# Control.net
KiCad netlist of a schematic drawn in EAGLE
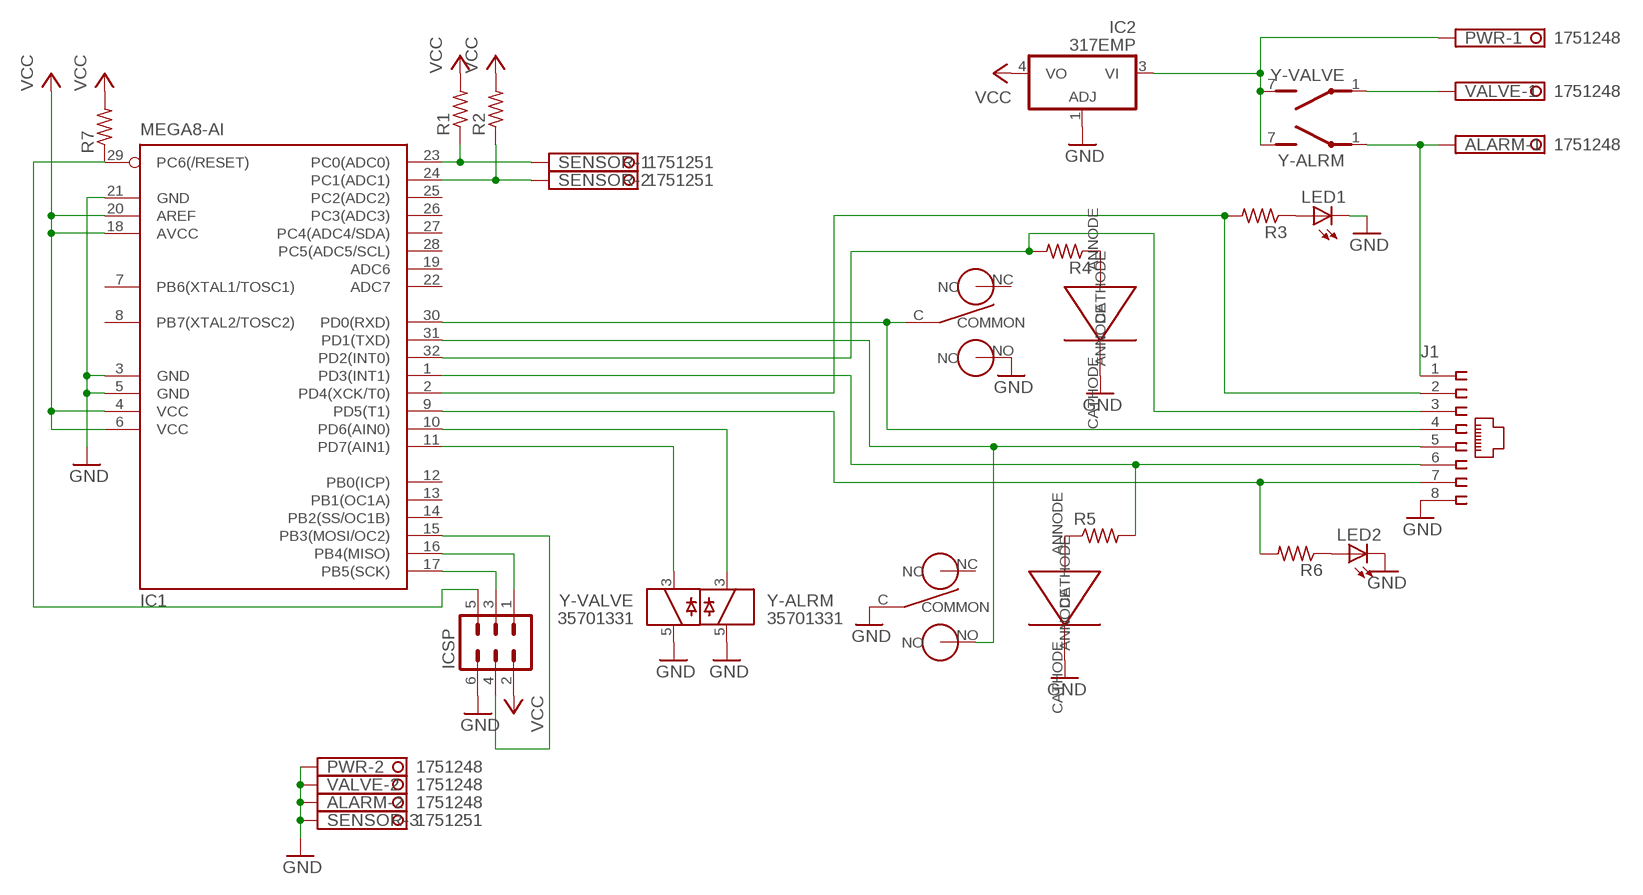
[diagram p0: schematic, sheet 1]

(export (version "E")
  (design (tool "Eeschema 10.0.6"))
  (components
    (comp (ref "ALARM")
      (value "1751248")
      (footprint "eagle-import:1751248")
      (libsource (lib "eagle-import") (part "1751248"))
    )
    (comp (ref "BUTTON1")
      (value "LED-BUTTON-16MM")
      (footprint "eagle-import:16MM")
      (libsource (lib "eagle-import") (part "LED-BUTTON-16MM"))
    )
    (comp (ref "BUTTON2")
      (value "LED-BUTTON-16MM")
      (footprint "eagle-import:16MM")
      (libsource (lib "eagle-import") (part "LED-BUTTON-16MM"))
    )
    (comp (ref "IC1")
      (value "MEGA8-AI")
      (footprint "eagle-import:TQFP32-08")
      (fields (field (name "MPN") "ATMEGA8-16AU"))
      (libsource (lib "eagle-import") (part "MEGA8-AI"))
    )
    (comp (ref "IC2")
      (value "317EMP")
      (footprint "eagle-import:SOT223")
      (libsource (lib "eagle-import") (part "317EMP"))
    )
    (comp (ref "ICSP")
      (value "MA03-2")
      (footprint "eagle-import:MA03-2")
      (libsource (lib "eagle-import") (part "MA03-2"))
    )
    (comp (ref "J1")
      (value "215877-7")
      (footprint "eagle-import:215877-7")
      (libsource (lib "eagle-import") (part "215877-7"))
    )
    (comp (ref "LED1")
      (value "LED5MM")
      (footprint "eagle-import:LED5MM")
      (libsource (lib "eagle-import") (part "LED5MM"))
    )
    (comp (ref "LED2")
      (value "LED5MM")
      (footprint "eagle-import:LED5MM")
      (libsource (lib "eagle-import") (part "LED5MM"))
    )
    (comp (ref "PWR")
      (value "1751248")
      (footprint "eagle-import:1751248")
      (libsource (lib "eagle-import") (part "1751248"))
    )
    (comp (ref "R1")
      (value "R-US_M0805")
      (footprint "eagle-import:M0805")
      (libsource (lib "eagle-import") (part "R-US_M0805"))
    )
    (comp (ref "R2")
      (value "R-US_M0805")
      (footprint "eagle-import:M0805")
      (libsource (lib "eagle-import") (part "R-US_M0805"))
    )
    (comp (ref "R3")
      (value "R-US_M0805")
      (footprint "eagle-import:M0805")
      (libsource (lib "eagle-import") (part "R-US_M0805"))
    )
    (comp (ref "R4")
      (value "R-US_M0805")
      (footprint "eagle-import:M0805")
      (libsource (lib "eagle-import") (part "R-US_M0805"))
    )
    (comp (ref "R5")
      (value "R-US_M0805")
      (footprint "eagle-import:M0805")
      (libsource (lib "eagle-import") (part "R-US_M0805"))
    )
    (comp (ref "R6")
      (value "R-US_M0805")
      (footprint "eagle-import:M0805")
      (libsource (lib "eagle-import") (part "R-US_M0805"))
    )
    (comp (ref "R7")
      (value "R-US_M0805")
      (footprint "eagle-import:M0805")
      (libsource (lib "eagle-import") (part "R-US_M0805"))
    )
    (comp (ref "SENSOR")
      (value "1751251")
      (footprint "eagle-import:1751251")
      (libsource (lib "eagle-import") (part "1751251"))
    )
    (comp (ref "VALVE")
      (value "1751248")
      (footprint "eagle-import:1751248")
      (libsource (lib "eagle-import") (part "1751248"))
    )
    (comp (ref "Y-ALRM")
      (value "35701331")
      (footprint "eagle-import:REED")
      (libsource (lib "eagle-import") (part "35701331"))
    )
    (comp (ref "Y-VALVE")
      (value "35701331")
      (footprint "eagle-import:REED")
      (libsource (lib "eagle-import") (part "35701331"))
    )
  )
  (nets
    (net (code "1") (name "GND") (class "Default")
      (node (ref "ALARM") (pin "2") (pinfunction "K_2") (pintype "passive"))
      (node (ref "BUTTON1") (pin "CATHODE") (pinfunction "CATHODE_CATHODE") (pintype "bidirectional"))
      (node (ref "BUTTON1") (pin "NO") (pinfunction "NO_NO") (pintype "bidirectional"))
      (node (ref "BUTTON2") (pin "C") (pinfunction "COMMON_C") (pintype "bidirectional"))
      (node (ref "BUTTON2") (pin "CATHODE") (pinfunction "CATHODE_CATHODE") (pintype "bidirectional"))
      (node (ref "IC1") (pin "21") (pinfunction "GND_21") (pintype "power_in"))
      (node (ref "IC1") (pin "3") (pinfunction "GND_3") (pintype "power_in"))
      (node (ref "IC1") (pin "5") (pinfunction "GND_5") (pintype "power_in"))
      (node (ref "IC2") (pin "1") (pinfunction "ADJ_1") (pintype "input"))
      (node (ref "ICSP") (pin "6") (pinfunction "6_6") (pintype "passive"))
      (node (ref "J1") (pin "8") (pinfunction "8_8") (pintype "passive"))
      (node (ref "LED1") (pin "K") (pinfunction "C_K") (pintype "passive"))
      (node (ref "LED2") (pin "K") (pinfunction "C_K") (pintype "passive"))
      (node (ref "PWR") (pin "2") (pinfunction "K_2") (pintype "passive"))
      (node (ref "SENSOR") (pin "3") (pinfunction "K_3") (pintype "passive"))
      (node (ref "VALVE") (pin "2") (pinfunction "K_2") (pintype "passive"))
      (node (ref "Y-ALRM") (pin "5") (pinfunction "5_5") (pintype "passive"))
      (node (ref "Y-VALVE") (pin "5") (pinfunction "5_5") (pintype "passive"))
    )
    (net (code "2") (name "Net-(ALARMA-K)") (class "Default")
      (node (ref "ALARM") (pin "1") (pinfunction "K_1") (pintype "passive"))
      (node (ref "J1") (pin "1") (pinfunction "1_1") (pintype "passive"))
      (node (ref "Y-ALRM") (pin "1") (pinfunction "P_1") (pintype "passive"))
    )
    (net (code "3") (name "Net-(BUTTON1-COMMON)") (class "Default")
      (node (ref "BUTTON1") (pin "C") (pinfunction "COMMON_C") (pintype "bidirectional"))
      (node (ref "IC1") (pin "30") (pinfunction "PD0(RXD)_30") (pintype "bidirectional"))
      (node (ref "J1") (pin "4") (pinfunction "4_4") (pintype "passive"))
    )
    (net (code "4") (name "Net-(BUTTON1-PadANNODE)") (class "Default")
      (node (ref "BUTTON1") (pin "ANNODE") (pinfunction "ANNODE_ANNODE") (pintype "bidirectional"))
      (node (ref "R4") (pin "1") (pinfunction "1_1") (pintype "passive"))
    )
    (net (code "5") (name "Net-(BUTTON2-PadANNODE)") (class "Default")
      (node (ref "BUTTON2") (pin "ANNODE") (pinfunction "ANNODE_ANNODE") (pintype "bidirectional"))
      (node (ref "R5") (pin "1") (pinfunction "1_1") (pintype "passive"))
    )
    (net (code "6") (name "Net-(IC1-PB3(MOSI{slash}OC2))") (class "Default")
      (node (ref "IC1") (pin "15") (pinfunction "PB3(MOSI/OC2)_15") (pintype "bidirectional"))
      (node (ref "ICSP") (pin "4") (pinfunction "4_4") (pintype "passive"))
    )
    (net (code "7") (name "Net-(IC1-PB4(MISO))") (class "Default")
      (node (ref "IC1") (pin "16") (pinfunction "PB4(MISO)_16") (pintype "bidirectional"))
      (node (ref "ICSP") (pin "1") (pinfunction "1_1") (pintype "passive"))
    )
    (net (code "8") (name "Net-(IC1-PB5(SCK))") (class "Default")
      (node (ref "IC1") (pin "17") (pinfunction "PB5(SCK)_17") (pintype "bidirectional"))
      (node (ref "ICSP") (pin "3") (pinfunction "3_3") (pintype "passive"))
    )
    (net (code "9") (name "Net-(IC1-PC0(ADC0))") (class "Default")
      (node (ref "IC1") (pin "23") (pinfunction "PC0(ADC0)_23") (pintype "bidirectional"))
      (node (ref "R1") (pin "1") (pinfunction "1_1") (pintype "passive"))
      (node (ref "SENSOR") (pin "1") (pinfunction "K_1") (pintype "passive"))
    )
    (net (code "10") (name "Net-(IC1-PC1(ADC1))") (class "Default")
      (node (ref "IC1") (pin "24") (pinfunction "PC1(ADC1)_24") (pintype "bidirectional"))
      (node (ref "R2") (pin "1") (pinfunction "1_1") (pintype "passive"))
      (node (ref "SENSOR") (pin "2") (pinfunction "K_2") (pintype "passive"))
    )
    (net (code "11") (name "Net-(IC1-PC6({slash}RESET))") (class "Default")
      (node (ref "IC1") (pin "29") (pinfunction "PC6(/RESET)_29") (pintype "bidirectional"))
      (node (ref "ICSP") (pin "5") (pinfunction "5_5") (pintype "passive"))
      (node (ref "R7") (pin "1") (pinfunction "1_1") (pintype "passive"))
    )
    (net (code "12") (name "Net-(IC1-PD1(TXD))") (class "Default")
      (node (ref "BUTTON2") (pin "NO") (pinfunction "NO_NO") (pintype "bidirectional"))
      (node (ref "IC1") (pin "31") (pinfunction "PD1(TXD)_31") (pintype "bidirectional"))
      (node (ref "J1") (pin "5") (pinfunction "5_5") (pintype "passive"))
    )
    (net (code "13") (name "Net-(IC1-PD2(INT0))") (class "Default")
      (node (ref "IC1") (pin "32") (pinfunction "PD2(INT0)_32") (pintype "bidirectional"))
      (node (ref "J1") (pin "3") (pinfunction "3_3") (pintype "passive"))
      (node (ref "R4") (pin "2") (pinfunction "2_2") (pintype "passive"))
    )
    (net (code "14") (name "Net-(IC1-PD3(INT1))") (class "Default")
      (node (ref "IC1") (pin "1") (pinfunction "PD3(INT1)_1") (pintype "bidirectional"))
      (node (ref "J1") (pin "6") (pinfunction "6_6") (pintype "passive"))
      (node (ref "R5") (pin "2") (pinfunction "2_2") (pintype "passive"))
    )
    (net (code "15") (name "Net-(IC1-PD4(XCK{slash}T0))") (class "Default")
      (node (ref "IC1") (pin "2") (pinfunction "PD4(XCK/T0)_2") (pintype "bidirectional"))
      (node (ref "J1") (pin "2") (pinfunction "2_2") (pintype "passive"))
      (node (ref "R3") (pin "2") (pinfunction "2_2") (pintype "passive"))
    )
    (net (code "16") (name "Net-(IC1-PD5(T1))") (class "Default")
      (node (ref "IC1") (pin "9") (pinfunction "PD5(T1)_9") (pintype "bidirectional"))
      (node (ref "J1") (pin "7") (pinfunction "7_7") (pintype "passive"))
      (node (ref "R6") (pin "2") (pinfunction "2_2") (pintype "passive"))
    )
    (net (code "17") (name "Net-(IC1-PD6(AIN0))") (class "Default")
      (node (ref "IC1") (pin "10") (pinfunction "PD6(AIN0)_10") (pintype "bidirectional"))
      (node (ref "Y-ALRM") (pin "3") (pinfunction "3_3") (pintype "passive"))
    )
    (net (code "18") (name "Net-(IC1-PD7(AIN1))") (class "Default")
      (node (ref "IC1") (pin "11") (pinfunction "PD7(AIN1)_11") (pintype "bidirectional"))
      (node (ref "Y-VALVE") (pin "3") (pinfunction "3_3") (pintype "passive"))
    )
    (net (code "19") (name "Net-(IC2-VI)") (class "Default")
      (node (ref "IC2") (pin "3") (pinfunction "VI_3") (pintype "input"))
      (node (ref "PWR") (pin "1") (pinfunction "K_1") (pintype "passive"))
      (node (ref "Y-ALRM") (pin "7") (pinfunction "S_7") (pintype "passive"))
      (node (ref "Y-VALVE") (pin "7") (pinfunction "S_7") (pintype "passive"))
    )
    (net (code "20") (name "Net-(LED1-PadA)") (class "Default")
      (node (ref "LED1") (pin "A") (pinfunction "A_A") (pintype "passive"))
      (node (ref "R3") (pin "1") (pinfunction "1_1") (pintype "passive"))
    )
    (net (code "21") (name "Net-(LED2-PadA)") (class "Default")
      (node (ref "LED2") (pin "A") (pinfunction "A_A") (pintype "passive"))
      (node (ref "R6") (pin "1") (pinfunction "1_1") (pintype "passive"))
    )
    (net (code "22") (name "Net-(VALVEA-K)") (class "Default")
      (node (ref "VALVE") (pin "1") (pinfunction "K_1") (pintype "passive"))
      (node (ref "Y-VALVE") (pin "1") (pinfunction "P_1") (pintype "passive"))
    )
    (net (code "23") (name "VCC") (class "Default")
      (node (ref "IC1") (pin "18") (pinfunction "AVCC_18") (pintype "power_in"))
      (node (ref "IC1") (pin "20") (pinfunction "AREF_20") (pintype "passive"))
      (node (ref "IC1") (pin "4") (pinfunction "VCC_4") (pintype "power_in"))
      (node (ref "IC1") (pin "6") (pinfunction "VCC_6") (pintype "power_in"))
      (node (ref "IC2") (pin "4") (pinfunction "VO_4") (pintype "passive"))
      (node (ref "ICSP") (pin "2") (pinfunction "2_2") (pintype "passive"))
      (node (ref "R1") (pin "2") (pinfunction "2_2") (pintype "passive"))
      (node (ref "R2") (pin "2") (pinfunction "2_2") (pintype "passive"))
      (node (ref "R7") (pin "2") (pinfunction "2_2") (pintype "passive"))
    )
    (net (code "24") (name "unconnected-(BUTTON1-PadNC)") (class "Default")
      (node (ref "BUTTON1") (pin "NC") (pinfunction "NC_NC") (pintype "bidirectional"))
    )
    (net (code "25") (name "unconnected-(BUTTON2-PadNC)") (class "Default")
      (node (ref "BUTTON2") (pin "NC") (pinfunction "NC_NC") (pintype "bidirectional"))
    )
    (net (code "26") (name "unconnected-(IC1-ADC6-Pad19)") (class "Default")
      (node (ref "IC1") (pin "19") (pinfunction "ADC6_19") (pintype "bidirectional"))
    )
    (net (code "27") (name "unconnected-(IC1-ADC7-Pad22)") (class "Default")
      (node (ref "IC1") (pin "22") (pinfunction "ADC7_22") (pintype "bidirectional"))
    )
    (net (code "28") (name "unconnected-(IC1-PB0(ICP)-Pad12)") (class "Default")
      (node (ref "IC1") (pin "12") (pinfunction "PB0(ICP)_12") (pintype "bidirectional"))
    )
    (net (code "29") (name "unconnected-(IC1-PB1(OC1A)-Pad13)") (class "Default")
      (node (ref "IC1") (pin "13") (pinfunction "PB1(OC1A)_13") (pintype "bidirectional"))
    )
    (net (code "30") (name "unconnected-(IC1-PB2(SS{slash}OC1B)-Pad14)") (class "Default")
      (node (ref "IC1") (pin "14") (pinfunction "PB2(SS/OC1B)_14") (pintype "bidirectional"))
    )
    (net (code "31") (name "unconnected-(IC1-PB6(XTAL1{slash}TOSC1)-Pad7)") (class "Default")
      (node (ref "IC1") (pin "7") (pinfunction "PB6(XTAL1/TOSC1)_7") (pintype "bidirectional"))
    )
    (net (code "32") (name "unconnected-(IC1-PB7(XTAL2{slash}TOSC2)-Pad8)") (class "Default")
      (node (ref "IC1") (pin "8") (pinfunction "PB7(XTAL2/TOSC2)_8") (pintype "bidirectional"))
    )
    (net (code "33") (name "unconnected-(IC1-PC2(ADC2)-Pad25)") (class "Default")
      (node (ref "IC1") (pin "25") (pinfunction "PC2(ADC2)_25") (pintype "bidirectional"))
    )
    (net (code "34") (name "unconnected-(IC1-PC3(ADC3)-Pad26)") (class "Default")
      (node (ref "IC1") (pin "26") (pinfunction "PC3(ADC3)_26") (pintype "bidirectional"))
    )
    (net (code "35") (name "unconnected-(IC1-PC4(ADC4{slash}SDA)-Pad27)") (class "Default")
      (node (ref "IC1") (pin "27") (pinfunction "PC4(ADC4/SDA)_27") (pintype "bidirectional"))
    )
    (net (code "36") (name "unconnected-(IC1-PC5(ADC5{slash}SCL)-Pad28)") (class "Default")
      (node (ref "IC1") (pin "28") (pinfunction "PC5(ADC5/SCL)_28") (pintype "bidirectional"))
    )
  )
)
